# LiDAR_mainboard.net
KiCad netlist of a schematic drawn in Altium Designer
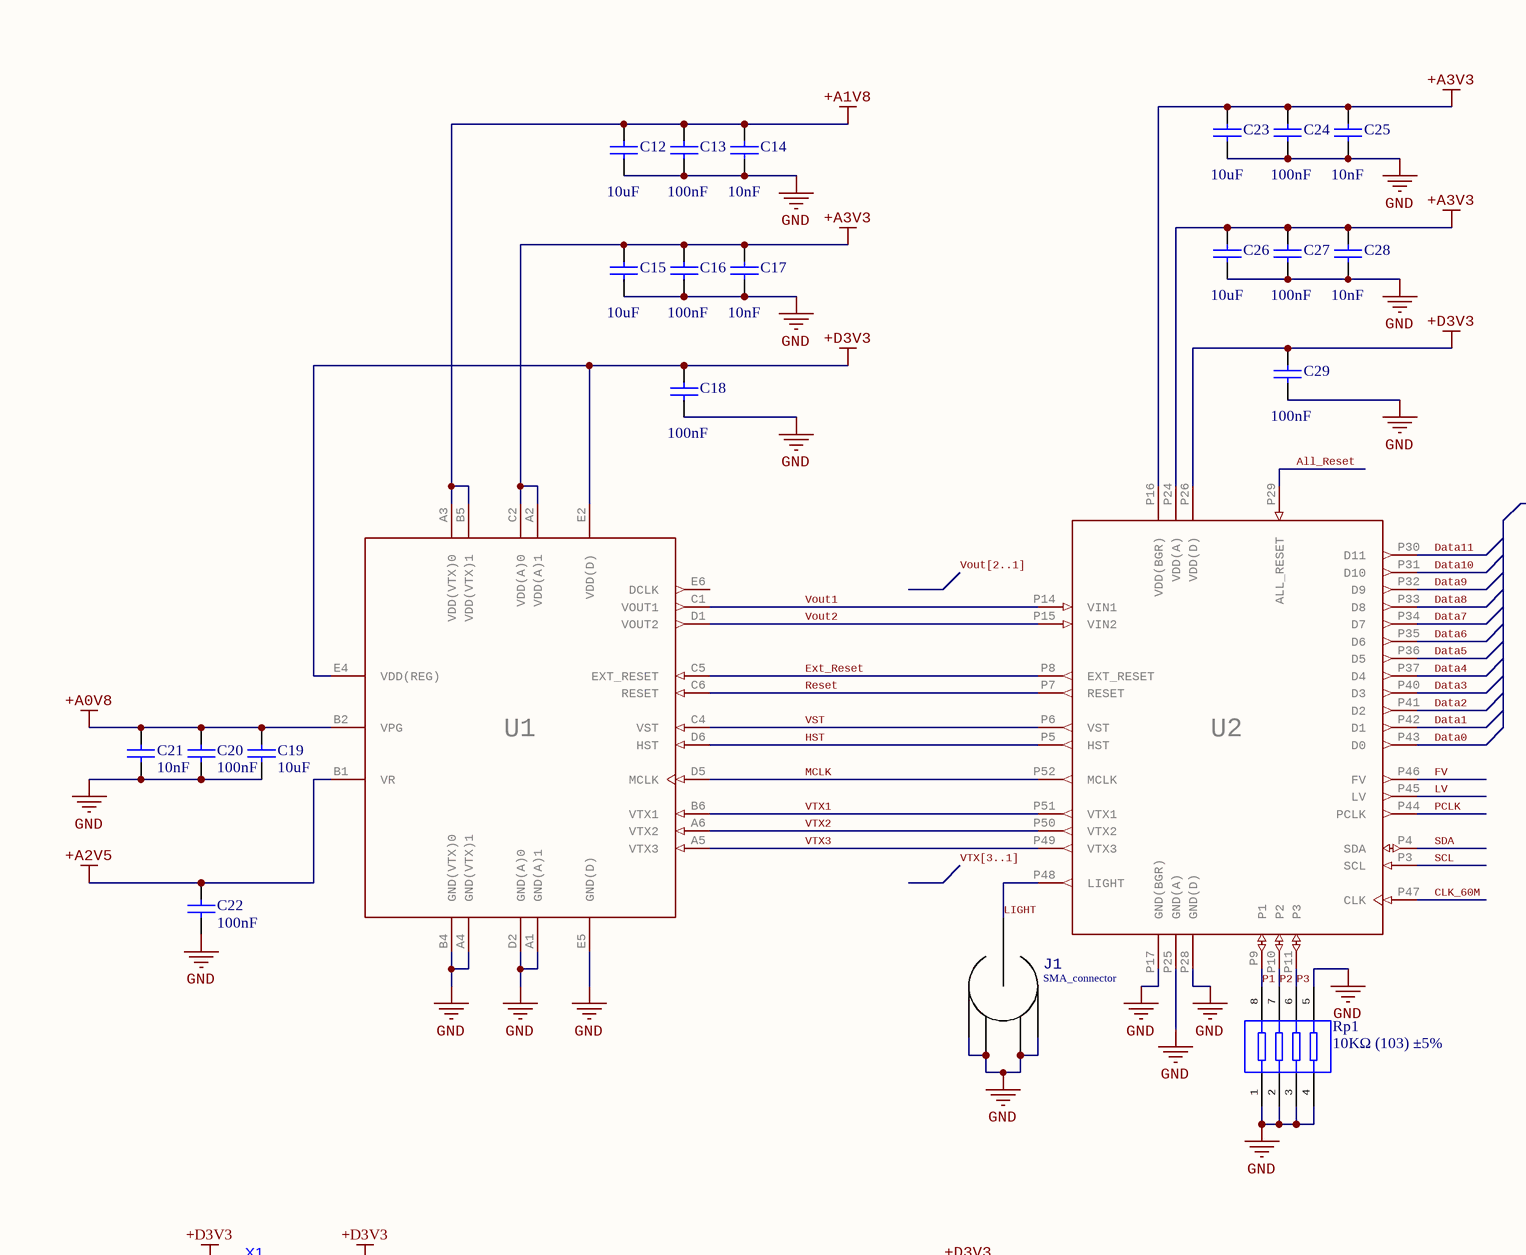
[diagram p0: LiDAR_mainboard.SchDoc, top left]
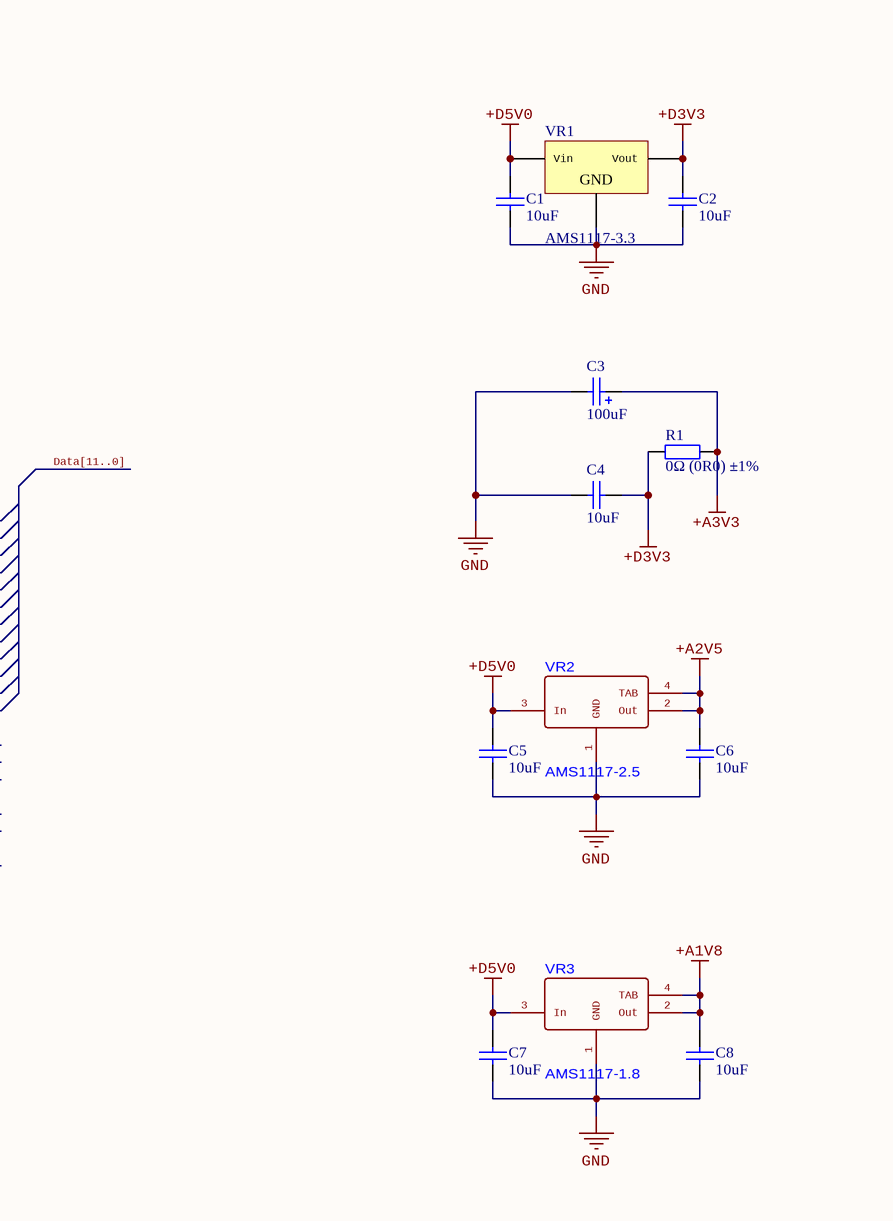
[diagram p1: LiDAR_mainboard.SchDoc, top right]
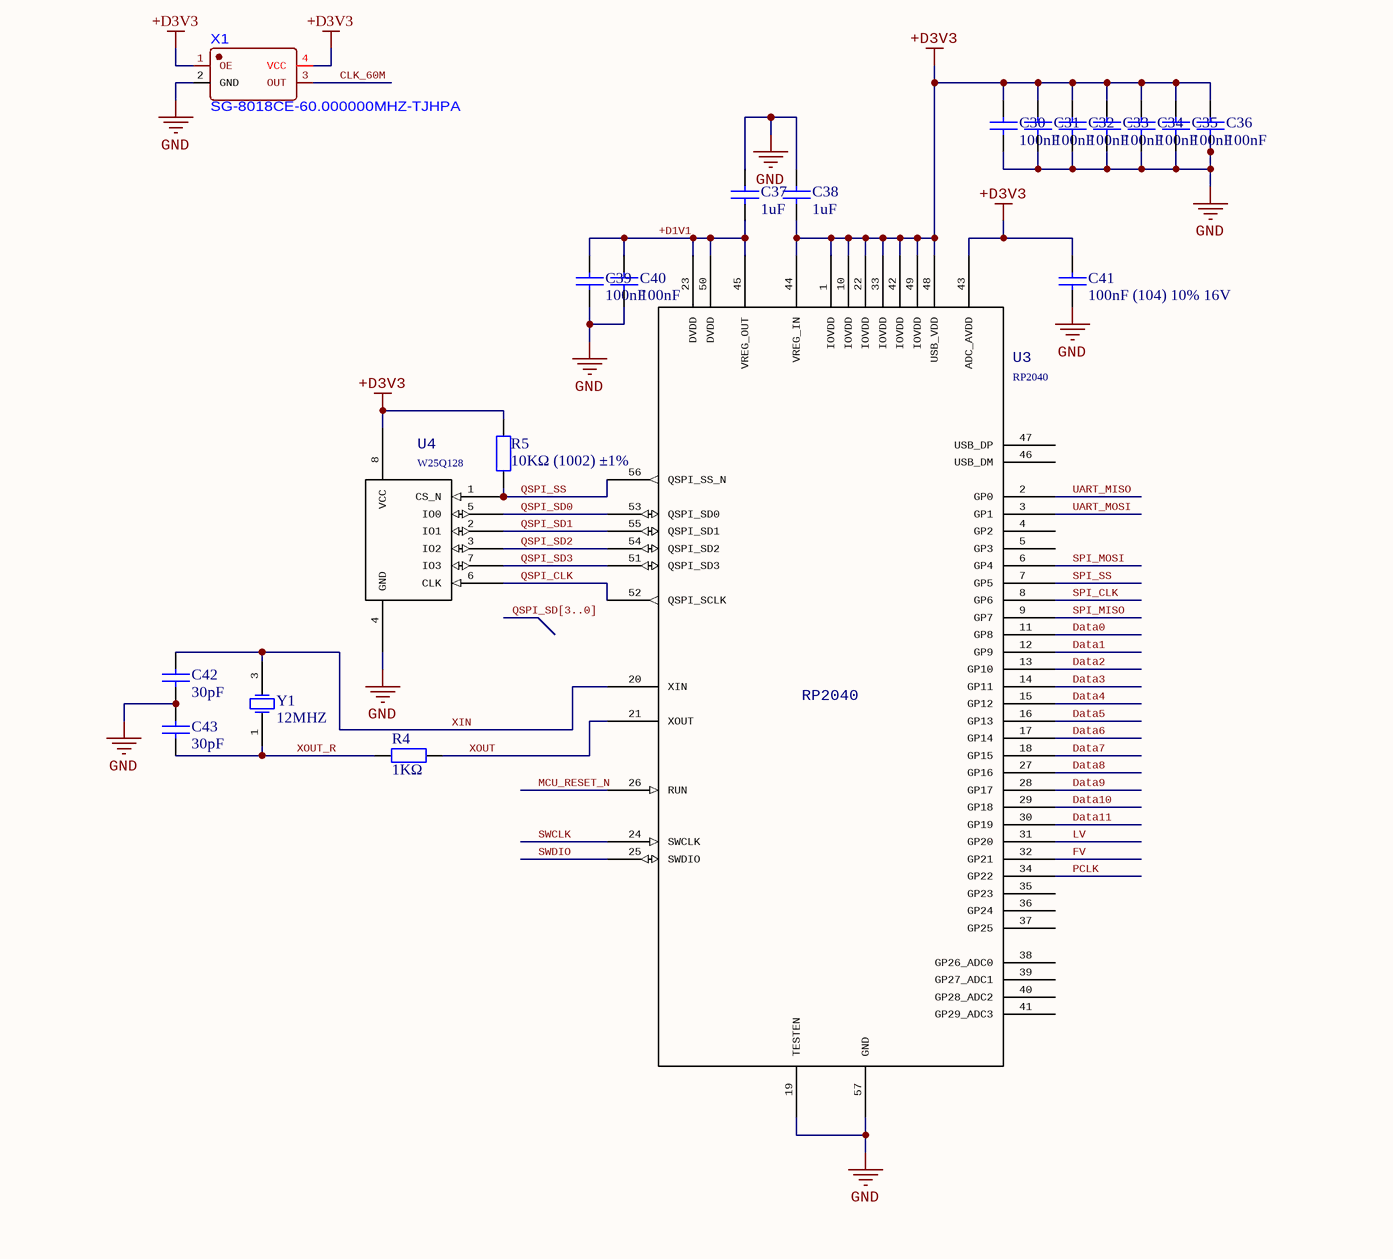
[diagram p2: LiDAR_mainboard.SchDoc, bottom left]
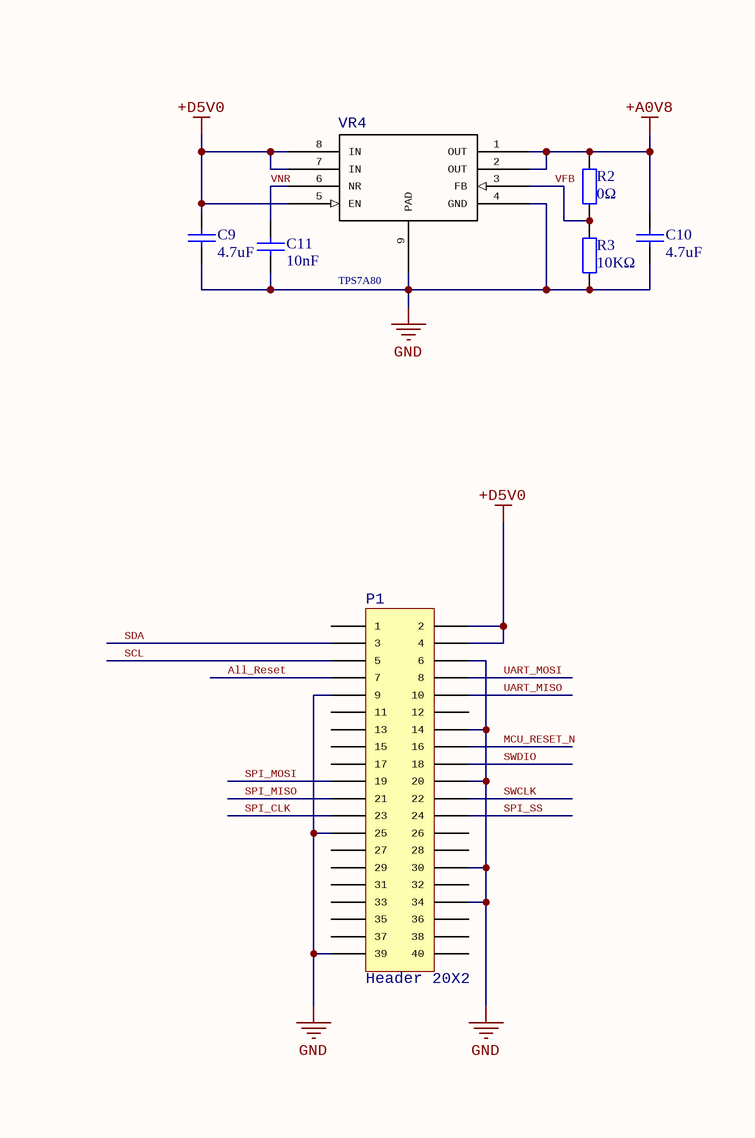
[diagram p3: LiDAR_mainboard.SchDoc, bottom right]

(export (version "E")
  (design (tool "Eeschema 10.0.6"))
  (components
    (comp (ref "C1")
      (value "10uF")
      (footprint "0402_C")
      (description "贴片电容")
      (libsource (lib "JLC SMT Devices") (part "0402 10uF (106) 20% 6.3V"))
    )
    (comp (ref "C2")
      (value "10uF")
      (footprint "0402_C")
      (description "贴片电容")
      (libsource (lib "JLC SMT Devices") (part "0402 10uF (106) 20% 6.3V"))
    )
    (comp (ref "C3")
      (value "100uF")
      (footprint "CASE-B_3528")
      (description "钽电容")
      (libsource (lib "JLC SMT Devices") (part "3528 100uF (107) 10% 6.3V"))
    )
    (comp (ref "C4")
      (value "10uF")
      (footprint "0603_C")
      (description "贴片电容")
      (libsource (lib "JLC SMT Devices") (part "0603 10uF (106) 10% 10V"))
    )
    (comp (ref "C5")
      (value "10uF")
      (footprint "0402_C")
      (description "贴片电容")
      (libsource (lib "JLC SMT Devices") (part "0402 10uF (106) 20% 6.3V"))
    )
    (comp (ref "C6")
      (value "10uF")
      (footprint "0402_C")
      (description "贴片电容")
      (libsource (lib "JLC SMT Devices") (part "0402 10uF (106) 20% 6.3V"))
    )
    (comp (ref "C7")
      (value "10uF")
      (footprint "0402_C")
      (description "贴片电容")
      (libsource (lib "JLC SMT Devices") (part "0402 10uF (106) 20% 6.3V"))
    )
    (comp (ref "C8")
      (value "10uF")
      (footprint "0402_C")
      (description "贴片电容")
      (libsource (lib "JLC SMT Devices") (part "0402 10uF (106) 20% 6.3V"))
    )
    (comp (ref "C9")
      (value "4.7uF")
      (footprint "0402_C")
      (description "贴片电容")
      (libsource (lib "JLC SMT Devices") (part "0402 4.7uF (475) 20% 10V"))
    )
    (comp (ref "C10")
      (value "4.7uF")
      (footprint "0402_C")
      (description "贴片电容")
      (libsource (lib "JLC SMT Devices") (part "0402 4.7uF (475) 20% 10V"))
    )
    (comp (ref "C11")
      (value "10nF")
      (footprint "0402_C")
      (description "贴片电容")
      (libsource (lib "JLC SMT Devices") (part "0402 10nF (103) 10% 50V"))
    )
    (comp (ref "C12")
      (value "10uF")
      (footprint "0402_C")
      (description "贴片电容")
      (libsource (lib "JLC SMT Devices") (part "0402 10uF (106) 20% 6.3V"))
    )
    (comp (ref "C13")
      (value "100nF")
      (footprint "0402_C")
      (description "贴片电容")
      (libsource (lib "JLC SMT Devices") (part "0402 100nF (104) 10% 16V"))
    )
    (comp (ref "C14")
      (value "10nF")
      (footprint "0402_C")
      (description "贴片电容")
      (libsource (lib "JLC SMT Devices") (part "0402 10nF (103) 10% 50V"))
    )
    (comp (ref "C15")
      (value "10uF")
      (footprint "0402_C")
      (description "贴片电容")
      (libsource (lib "JLC SMT Devices") (part "0402 10uF (106) 20% 6.3V"))
    )
    (comp (ref "C16")
      (value "100nF")
      (footprint "0402_C")
      (description "贴片电容")
      (libsource (lib "JLC SMT Devices") (part "0402 100nF (104) 10% 16V"))
    )
    (comp (ref "C17")
      (value "10nF")
      (footprint "0402_C")
      (description "贴片电容")
      (libsource (lib "JLC SMT Devices") (part "0402 10nF (103) 10% 50V"))
    )
    (comp (ref "C18")
      (value "100nF")
      (footprint "0402_C")
      (description "贴片电容")
      (libsource (lib "JLC SMT Devices") (part "0402 100nF (104) 10% 16V"))
    )
    (comp (ref "C19")
      (value "10uF")
      (footprint "0402_C")
      (description "贴片电容")
      (libsource (lib "JLC SMT Devices") (part "0402 10uF (106) 20% 6.3V"))
    )
    (comp (ref "C20")
      (value "100nF")
      (footprint "0402_C")
      (description "贴片电容")
      (libsource (lib "JLC SMT Devices") (part "0402 100nF (104) 10% 16V"))
    )
    (comp (ref "C21")
      (value "10nF")
      (footprint "0402_C")
      (description "贴片电容")
      (libsource (lib "JLC SMT Devices") (part "0402 10nF (103) 10% 50V"))
    )
    (comp (ref "C22")
      (value "100nF")
      (footprint "0402_C")
      (description "贴片电容")
      (libsource (lib "JLC SMT Devices") (part "0402 100nF (104) 10% 16V"))
    )
    (comp (ref "C23")
      (value "10uF")
      (footprint "0402_C")
      (description "贴片电容")
      (libsource (lib "JLC SMT Devices") (part "0402 10uF (106) 20% 6.3V"))
    )
    (comp (ref "C24")
      (value "100nF")
      (footprint "0402_C")
      (description "贴片电容")
      (libsource (lib "JLC SMT Devices") (part "0402 100nF (104) 10% 16V"))
    )
    (comp (ref "C25")
      (value "10nF")
      (footprint "0402_C")
      (description "贴片电容")
      (libsource (lib "JLC SMT Devices") (part "0402 10nF (103) 10% 50V"))
    )
    (comp (ref "C26")
      (value "10uF")
      (footprint "0402_C")
      (description "贴片电容")
      (libsource (lib "JLC SMT Devices") (part "0402 10uF (106) 20% 6.3V"))
    )
    (comp (ref "C27")
      (value "100nF")
      (footprint "0402_C")
      (description "贴片电容")
      (libsource (lib "JLC SMT Devices") (part "0402 100nF (104) 10% 16V"))
    )
    (comp (ref "C28")
      (value "10nF")
      (footprint "0402_C")
      (description "贴片电容")
      (libsource (lib "JLC SMT Devices") (part "0402 10nF (103) 10% 50V"))
    )
    (comp (ref "C29")
      (value "100nF")
      (footprint "0402_C")
      (description "贴片电容")
      (libsource (lib "JLC SMT Devices") (part "0402 100nF (104) 10% 16V"))
    )
    (comp (ref "C30")
      (value "100nF")
      (footprint "0402_C")
      (description "贴片电容")
      (libsource (lib "JLC SMT Devices") (part "0402 100nF (104) 10% 16V"))
    )
    (comp (ref "C31")
      (value "100nF")
      (footprint "0402_C")
      (description "贴片电容")
      (libsource (lib "JLC SMT Devices") (part "0402 100nF (104) 10% 16V"))
    )
    (comp (ref "C32")
      (value "100nF")
      (footprint "0402_C")
      (description "贴片电容")
      (libsource (lib "JLC SMT Devices") (part "0402 100nF (104) 10% 16V"))
    )
    (comp (ref "C33")
      (value "100nF")
      (footprint "0402_C")
      (description "贴片电容")
      (libsource (lib "JLC SMT Devices") (part "0402 100nF (104) 10% 16V"))
    )
    (comp (ref "C34")
      (value "100nF")
      (footprint "0402_C")
      (description "贴片电容")
      (libsource (lib "JLC SMT Devices") (part "0402 100nF (104) 10% 16V"))
    )
    (comp (ref "C35")
      (value "100nF")
      (footprint "0402_C")
      (description "贴片电容")
      (libsource (lib "JLC SMT Devices") (part "0402 100nF (104) 10% 16V"))
    )
    (comp (ref "C36")
      (value "100nF")
      (footprint "0402_C")
      (description "贴片电容")
      (libsource (lib "JLC SMT Devices") (part "0402 100nF (104) 10% 16V"))
    )
    (comp (ref "C37")
      (value "1uF")
      (footprint "0603_C")
      (description "贴片电容")
      (libsource (lib "JLC SMT Devices") (part "0603 1uF (105) 10% 50V"))
    )
    (comp (ref "C38")
      (value "1uF")
      (footprint "0603_C")
      (description "贴片电容")
      (libsource (lib "JLC SMT Devices") (part "0603 1uF (105) 10% 50V"))
    )
    (comp (ref "C39")
      (value "100nF")
      (footprint "0402_C")
      (description "贴片电容")
      (libsource (lib "JLC SMT Devices") (part "0402 100nF (104) 10% 16V"))
    )
    (comp (ref "C40")
      (value "100nF")
      (footprint "0402_C")
      (description "贴片电容")
      (libsource (lib "JLC SMT Devices") (part "0402 100nF (104) 10% 16V"))
    )
    (comp (ref "C41")
      (value "100nF (104) 10% 16V")
      (footprint "0402_C")
      (description "贴片电容")
      (libsource (lib "JLC SMT Devices") (part "0402 100nF (104) 10% 16V"))
    )
    (comp (ref "C42")
      (value "30pF")
      (footprint "0402_C")
      (description "贴片电容")
      (libsource (lib "JLC SMT Devices") (part "0402 30pF (300) 5% 50V"))
    )
    (comp (ref "C43")
      (value "30pF")
      (footprint "0402_C")
      (description "贴片电容")
      (libsource (lib "JLC SMT Devices") (part "0402 30pF (300) 5% 50V"))
    )
    (comp (ref "J1")
      (value "SMA_connector")
      (footprint "SMA_header")
      (libsource (lib "SMA connector") (part "SMA_connector"))
    )
    (comp (ref "P1")
      (value "Header 20X2")
      (footprint "HDR2X20")
      (description "Header, 20-Pin, Dual row")
      (fields (field (name "PUBLISHER") "Altium Limited"))
      (libsource (lib "Miscellaneous Connectors") (part "Header 20X2"))
    )
    (comp (ref "R1")
      (value "0Ω (0R0) ±1%")
      (footprint "0805_R")
      (description "贴片电阻")
      (libsource (lib "JLC SMT Devices") (part "0805 0Ω (0R0) 1%"))
    )
    (comp (ref "R2")
      (value "0Ω")
      (footprint "0603_R")
      (description "贴片电阻")
      (libsource (lib "JLC SMT Devices") (part "0603 0Ω (0R0) 1%"))
    )
    (comp (ref "R3")
      (value "10KΩ")
      (footprint "0603_R")
      (description "贴片电阻")
      (libsource (lib "JLC SMT Devices") (part "0603 10KΩ (1002) 1%"))
    )
    (comp (ref "R4")
      (value "1KΩ")
      (footprint "0402_R")
      (description "贴片电阻")
      (libsource (lib "JLC SMT Devices") (part "0402 1KΩ (1001) 1%"))
    )
    (comp (ref "R5")
      (value "10KΩ (1002) ±1%")
      (footprint "0603_R")
      (description "贴片电阻")
      (libsource (lib "JLC SMT Devices") (part "0603 10KΩ (1002) 1%"))
    )
    (comp (ref "Rp1")
      (value "10KΩ (103) ±5%")
      (footprint "0402_Rx4")
      (description "贴片排阻")
      (libsource (lib "JLC SMT Devices") (part "0402*4 10KΩ (103) 5%"))
    )
    (comp (ref "U1")
      (value "S15454-01WT Distance Area Image Sensor")
      (footprint "S15454-01WT")
      (description "Hamamatsu area distance image sensor")
      (libsource (lib "Hamamatsu Distance Image Sensors") (part "S15454-01WT"))
    )
    (comp (ref "U2")
      (value "H15472-01")
      (footprint "H15472-01")
      (description "ASIC for distance image sensors")
      (libsource (lib "Hamamatsu Distance Image Sensors") (part "H15472-01"))
    )
    (comp (ref "U3") (value "RP2040") (footprint "QFN-56") (libsource (lib "RP2040") (part "RP2040")))
    (comp (ref "U4") (value "W25Q128") (footprint "SOIC-8") (libsource (lib "W25Q128") (part "W25Q128")))
    (comp (ref "VR1")
      (value "AMS1117-3.3")
      (footprint "SOT-223")
      (description "低压差线性稳压(LDO)")
      (libsource (lib "JLC SMT Devices") (part "SOT-223 AMS1117-3.3"))
    )
    (comp (ref "VR2")
      (value "AMS1117-2.5")
      (footprint "SOT-223-4_L6.5-W3.5-P2.30-LS7.0-BR")
      (libsource (lib "AMS1117-2.5") (part "AMS1117-2.5"))
    )
    (comp (ref "VR3")
      (value "AMS1117-1.8")
      (footprint "SOT-223-4_L6.5-W3.5-P2.30-LS7.0-BR")
      (libsource (lib "AMS1117-1.8") (part "AMS1117-1.8"))
    )
    (comp (ref "VR4") (value "TPS7A80") (footprint "SON_8") (libsource (lib "TPS7A80") (part "TPS7A80")))
    (comp (ref "X1")
      (value "SG-8018CE-60.000000MHZ-TJHPA")
      (footprint "OSC-SMD_4P-L3.2-W2.5-BL_SIT8008BI")
      (libsource (lib "SG-8018CE-60.000000MHZ-TJHPA") (part "SG-8018CE-60.000000MHZ-TJHPA"))
    )
    (comp (ref "Y1")
      (value "12MHZ")
      (footprint "SMD-3225_4P")
      (description "贴片晶振")
      (libsource (lib "JLC SMT Devices") (part "SMD-3225_4P  12MHZ 20PF 10PPM"))
    )
  )
  (nets
    (net (code "1") (name "+A0V8") (class "Default")
      (node (ref "C10") (pin "2") (pinfunction "2_2") (pintype "passive"))
      (node (ref "C19") (pin "2") (pinfunction "2_2") (pintype "passive"))
      (node (ref "C20") (pin "2") (pinfunction "2_2") (pintype "passive"))
      (node (ref "C21") (pin "2") (pinfunction "2_2") (pintype "passive"))
      (node (ref "R2") (pin "2") (pinfunction "2_2") (pintype "passive"))
      (node (ref "U1") (pin "B2") (pinfunction "VPG_B2") (pintype "power_in"))
      (node (ref "VR4") (pin "1") (pinfunction "OUT_1") (pintype "power_in"))
      (node (ref "VR4") (pin "2") (pinfunction "OUT_2") (pintype "power_in"))
    )
    (net (code "2") (name "+A1V8") (class "Default")
      (node (ref "C12") (pin "2") (pinfunction "2_2") (pintype "passive"))
      (node (ref "C13") (pin "2") (pinfunction "2_2") (pintype "passive"))
      (node (ref "C14") (pin "2") (pinfunction "2_2") (pintype "passive"))
      (node (ref "C8") (pin "2") (pinfunction "2_2") (pintype "passive"))
      (node (ref "U1") (pin "A3") (pinfunction "VDD(VTX)0_A3") (pintype "power_in"))
      (node (ref "U1") (pin "B5") (pinfunction "VDD(VTX)1_B5") (pintype "power_in"))
      (node (ref "VR3") (pin "2") (pinfunction "Out_2") (pintype "passive"))
      (node (ref "VR3") (pin "4") (pinfunction "TAB_4") (pintype "passive"))
    )
    (net (code "3") (name "+A2V5") (class "Default")
      (node (ref "C22") (pin "2") (pinfunction "2_2") (pintype "passive"))
      (node (ref "C6") (pin "2") (pinfunction "2_2") (pintype "passive"))
      (node (ref "U1") (pin "B1") (pinfunction "VR_B1") (pintype "power_in"))
      (node (ref "VR2") (pin "2") (pinfunction "Out_2") (pintype "passive"))
      (node (ref "VR2") (pin "4") (pinfunction "TAB_4") (pintype "passive"))
    )
    (net (code "4") (name "+A3V3") (class "Default")
      (node (ref "C15") (pin "2") (pinfunction "2_2") (pintype "passive"))
      (node (ref "C16") (pin "2") (pinfunction "2_2") (pintype "passive"))
      (node (ref "C17") (pin "2") (pinfunction "2_2") (pintype "passive"))
      (node (ref "C23") (pin "2") (pinfunction "2_2") (pintype "passive"))
      (node (ref "C24") (pin "2") (pinfunction "2_2") (pintype "passive"))
      (node (ref "C25") (pin "2") (pinfunction "2_2") (pintype "passive"))
      (node (ref "C26") (pin "2") (pinfunction "2_2") (pintype "passive"))
      (node (ref "C27") (pin "2") (pinfunction "2_2") (pintype "passive"))
      (node (ref "C28") (pin "2") (pinfunction "2_2") (pintype "passive"))
      (node (ref "C3") (pin "1") (pinfunction "1_1") (pintype "passive"))
      (node (ref "R1") (pin "2") (pinfunction "2_2") (pintype "passive"))
      (node (ref "U1") (pin "A2") (pinfunction "VDD(A)1_A2") (pintype "power_in"))
      (node (ref "U1") (pin "C2") (pinfunction "VDD(A)0_C2") (pintype "power_in"))
      (node (ref "U2") (pin "P16") (pinfunction "VDD(BGR)_P16") (pintype "power_in"))
      (node (ref "U2") (pin "P24") (pinfunction "VDD(A)_P24") (pintype "power_in"))
    )
    (net (code "5") (name "+D3V3") (class "Default")
      (node (ref "C18") (pin "2") (pinfunction "2_2") (pintype "passive"))
      (node (ref "C2") (pin "2") (pinfunction "2_2") (pintype "passive"))
      (node (ref "C29") (pin "2") (pinfunction "2_2") (pintype "passive"))
      (node (ref "C30") (pin "2") (pinfunction "2_2") (pintype "passive"))
      (node (ref "C31") (pin "2") (pinfunction "2_2") (pintype "passive"))
      (node (ref "C32") (pin "2") (pinfunction "2_2") (pintype "passive"))
      (node (ref "C33") (pin "2") (pinfunction "2_2") (pintype "passive"))
      (node (ref "C34") (pin "2") (pinfunction "2_2") (pintype "passive"))
      (node (ref "C35") (pin "2") (pinfunction "2_2") (pintype "passive"))
      (node (ref "C36") (pin "2") (pinfunction "2_2") (pintype "passive"))
      (node (ref "C38") (pin "1") (pinfunction "1_1") (pintype "passive"))
      (node (ref "C4") (pin "1") (pinfunction "1_1") (pintype "passive"))
      (node (ref "C41") (pin "2") (pinfunction "2_2") (pintype "passive"))
      (node (ref "R1") (pin "1") (pinfunction "1_1") (pintype "passive"))
      (node (ref "R5") (pin "2") (pinfunction "2_2") (pintype "passive"))
      (node (ref "U1") (pin "E2") (pinfunction "VDD(D)_E2") (pintype "power_in"))
      (node (ref "U1") (pin "E4") (pinfunction "VDD(REG)_E4") (pintype "power_in"))
      (node (ref "U2") (pin "P26") (pinfunction "VDD(D)_P26") (pintype "power_in"))
      (node (ref "U3") (pin "1") (pinfunction "IOVDD_1") (pintype "power_in"))
      (node (ref "U3") (pin "10") (pinfunction "IOVDD_10") (pintype "power_in"))
      (node (ref "U3") (pin "22") (pinfunction "IOVDD_22") (pintype "power_in"))
      (node (ref "U3") (pin "33") (pinfunction "IOVDD_33") (pintype "power_in"))
      (node (ref "U3") (pin "42") (pinfunction "IOVDD_42") (pintype "power_in"))
      (node (ref "U3") (pin "43") (pinfunction "ADC_AVDD_43") (pintype "power_in"))
      (node (ref "U3") (pin "44") (pinfunction "VREG_IN_44") (pintype "power_in"))
      (node (ref "U3") (pin "48") (pinfunction "USB_VDD_48") (pintype "power_in"))
      (node (ref "U3") (pin "49") (pinfunction "IOVDD_49") (pintype "power_in"))
      (node (ref "U4") (pin "8") (pinfunction "VCC_8") (pintype "power_in"))
      (node (ref "VR1") (pin "2") (pinfunction "Vout_2") (pintype "passive"))
      (node (ref "X1") (pin "1") (pinfunction "OE_1") (pintype "passive"))
      (node (ref "X1") (pin "4") (pinfunction "VCC_4") (pintype "passive"))
    )
    (net (code "6") (name "+D5V0") (class "Default")
      (node (ref "C1") (pin "2") (pinfunction "2_2") (pintype "passive"))
      (node (ref "C5") (pin "2") (pinfunction "2_2") (pintype "passive"))
      (node (ref "C7") (pin "2") (pinfunction "2_2") (pintype "passive"))
      (node (ref "C9") (pin "2") (pinfunction "2_2") (pintype "passive"))
      (node (ref "P1") (pin "2") (pinfunction "2_2") (pintype "passive"))
      (node (ref "P1") (pin "4") (pinfunction "4_4") (pintype "passive"))
      (node (ref "VR1") (pin "3") (pinfunction "Vin_3") (pintype "passive"))
      (node (ref "VR2") (pin "3") (pinfunction "In_3") (pintype "passive"))
      (node (ref "VR3") (pin "3") (pinfunction "In_3") (pintype "passive"))
      (node (ref "VR4") (pin "5") (pinfunction "EN_5") (pintype "input"))
      (node (ref "VR4") (pin "7") (pinfunction "IN_7") (pintype "power_in"))
      (node (ref "VR4") (pin "8") (pinfunction "IN_8") (pintype "power_in"))
    )
    (net (code "7") (name "/+D1V1") (class "Default")
      (node (ref "C37") (pin "1") (pinfunction "1_1") (pintype "passive"))
      (node (ref "C39") (pin "2") (pinfunction "2_2") (pintype "passive"))
      (node (ref "C40") (pin "2") (pinfunction "2_2") (pintype "passive"))
      (node (ref "U3") (pin "23") (pinfunction "DVDD_23") (pintype "power_in"))
      (node (ref "U3") (pin "45") (pinfunction "VREG_OUT_45") (pintype "power_in"))
      (node (ref "U3") (pin "50") (pinfunction "DVDD_50") (pintype "power_in"))
    )
    (net (code "8") (name "/All_Reset") (class "Default")
      (node (ref "P1") (pin "7") (pinfunction "7_7") (pintype "passive"))
      (node (ref "U2") (pin "P29") (pinfunction "ALL_RESET_P29") (pintype "input"))
    )
    (net (code "9") (name "/CLK_60M") (class "Default")
      (node (ref "U2") (pin "P47") (pinfunction "CLK_P47") (pintype "input"))
      (node (ref "X1") (pin "3") (pinfunction "OUT_3") (pintype "passive"))
    )
    (net (code "10") (name "/Data0") (class "Default")
      (node (ref "U2") (pin "P43") (pinfunction "D0_P43") (pintype "output"))
      (node (ref "U3") (pin "11") (pinfunction "GP8_11") (pintype "passive"))
    )
    (net (code "11") (name "/Data1") (class "Default")
      (node (ref "U2") (pin "P42") (pinfunction "D1_P42") (pintype "output"))
      (node (ref "U3") (pin "12") (pinfunction "GP9_12") (pintype "passive"))
    )
    (net (code "12") (name "/Data2") (class "Default")
      (node (ref "U2") (pin "P41") (pinfunction "D2_P41") (pintype "output"))
      (node (ref "U3") (pin "13") (pinfunction "GP10_13") (pintype "passive"))
    )
    (net (code "13") (name "/Data3") (class "Default")
      (node (ref "U2") (pin "P40") (pinfunction "D3_P40") (pintype "output"))
      (node (ref "U3") (pin "14") (pinfunction "GP11_14") (pintype "passive"))
    )
    (net (code "14") (name "/Data4") (class "Default")
      (node (ref "U2") (pin "P37") (pinfunction "D4_P37") (pintype "output"))
      (node (ref "U3") (pin "15") (pinfunction "GP12_15") (pintype "passive"))
    )
    (net (code "15") (name "/Data5") (class "Default")
      (node (ref "U2") (pin "P36") (pinfunction "D5_P36") (pintype "output"))
      (node (ref "U3") (pin "16") (pinfunction "GP13_16") (pintype "passive"))
    )
    (net (code "16") (name "/Data6") (class "Default")
      (node (ref "U2") (pin "P35") (pinfunction "D6_P35") (pintype "output"))
      (node (ref "U3") (pin "17") (pinfunction "GP14_17") (pintype "passive"))
    )
    (net (code "17") (name "/Data7") (class "Default")
      (node (ref "U2") (pin "P34") (pinfunction "D7_P34") (pintype "output"))
      (node (ref "U3") (pin "18") (pinfunction "GP15_18") (pintype "passive"))
    )
    (net (code "18") (name "/Data8") (class "Default")
      (node (ref "U2") (pin "P33") (pinfunction "D8_P33") (pintype "output"))
      (node (ref "U3") (pin "27") (pinfunction "GP16_27") (pintype "passive"))
    )
    (net (code "19") (name "/Data9") (class "Default")
      (node (ref "U2") (pin "P32") (pinfunction "D9_P32") (pintype "output"))
      (node (ref "U3") (pin "28") (pinfunction "GP17_28") (pintype "passive"))
    )
    (net (code "20") (name "/Data10") (class "Default")
      (node (ref "U2") (pin "P31") (pinfunction "D10_P31") (pintype "output"))
      (node (ref "U3") (pin "29") (pinfunction "GP18_29") (pintype "passive"))
    )
    (net (code "21") (name "/Data11") (class "Default")
      (node (ref "U2") (pin "P30") (pinfunction "D11_P30") (pintype "output"))
      (node (ref "U3") (pin "30") (pinfunction "GP19_30") (pintype "passive"))
    )
    (net (code "23") (name "/Ext_Reset") (class "Default")
      (node (ref "U1") (pin "C5") (pinfunction "EXT_RESET_C5") (pintype "input"))
      (node (ref "U2") (pin "P8") (pinfunction "EXT_RESET_P8") (pintype "output"))
    )
    (net (code "24") (name "/FV") (class "Default")
      (node (ref "U2") (pin "P46") (pinfunction "FV_P46") (pintype "output"))
      (node (ref "U3") (pin "32") (pinfunction "GP21_32") (pintype "passive"))
    )
    (net (code "25") (name "/HST") (class "Default")
      (node (ref "U1") (pin "D6") (pinfunction "HST_D6") (pintype "input"))
      (node (ref "U2") (pin "P5") (pinfunction "HST_P5") (pintype "output"))
    )
    (net (code "26") (name "/LIGHT") (class "Default")
      (node (ref "J1") (pin "1") (pinfunction "CORE_1") (pintype "passive"))
      (node (ref "U2") (pin "P48") (pinfunction "LIGHT_P48") (pintype "output"))
    )
    (net (code "27") (name "/LV") (class "Default")
      (node (ref "U2") (pin "P45") (pinfunction "LV_P45") (pintype "output"))
      (node (ref "U3") (pin "31") (pinfunction "GP20_31") (pintype "passive"))
    )
    (net (code "28") (name "/MCLK") (class "Default")
      (node (ref "U1") (pin "D5") (pinfunction "MCLK_D5") (pintype "input"))
      (node (ref "U2") (pin "P52") (pinfunction "MCLK_P52") (pintype "output"))
    )
    (net (code "29") (name "/MCU_RESET_N") (class "Default")
      (node (ref "P1") (pin "16") (pinfunction "16_16") (pintype "passive"))
      (node (ref "U3") (pin "26") (pinfunction "RUN_26") (pintype "input"))
    )
    (net (code "30") (name "/P1") (class "Default")
      (node (ref "Rp1") (pin "8") (pinfunction "8_8") (pintype "passive"))
      (node (ref "U2") (pin "P9") (pinfunction "P1_P9") (pintype "bidirectional"))
    )
    (net (code "31") (name "/P2") (class "Default")
      (node (ref "Rp1") (pin "7") (pinfunction "7_7") (pintype "passive"))
      (node (ref "U2") (pin "P10") (pinfunction "P2_P10") (pintype "bidirectional"))
    )
    (net (code "32") (name "/P3") (class "Default")
      (node (ref "Rp1") (pin "6") (pinfunction "6_6") (pintype "passive"))
      (node (ref "U2") (pin "P11") (pinfunction "P3_P11") (pintype "bidirectional"))
    )
    (net (code "33") (name "/PCLK") (class "Default")
      (node (ref "U2") (pin "P44") (pinfunction "PCLK_P44") (pintype "output"))
      (node (ref "U3") (pin "34") (pinfunction "GP22_34") (pintype "passive"))
    )
    (net (code "34") (name "/QSPI_CLK") (class "Default")
      (node (ref "U3") (pin "52") (pinfunction "QSPI_SCLK_52") (pintype "output"))
      (node (ref "U4") (pin "6") (pinfunction "CLK_6") (pintype "input"))
    )
    (net (code "35") (name "/QSPI_SD0") (class "Default")
      (node (ref "U3") (pin "53") (pinfunction "QSPI_SD0_53") (pintype "bidirectional"))
      (node (ref "U4") (pin "5") (pinfunction "IO0_5") (pintype "bidirectional"))
    )
    (net (code "36") (name "/QSPI_SD1") (class "Default")
      (node (ref "U3") (pin "55") (pinfunction "QSPI_SD1_55") (pintype "bidirectional"))
      (node (ref "U4") (pin "2") (pinfunction "IO1_2") (pintype "bidirectional"))
    )
    (net (code "37") (name "/QSPI_SD2") (class "Default")
      (node (ref "U3") (pin "54") (pinfunction "QSPI_SD2_54") (pintype "bidirectional"))
      (node (ref "U4") (pin "3") (pinfunction "IO2_3") (pintype "bidirectional"))
    )
    (net (code "38") (name "/QSPI_SD3") (class "Default")
      (node (ref "U3") (pin "51") (pinfunction "QSPI_SD3_51") (pintype "bidirectional"))
      (node (ref "U4") (pin "7") (pinfunction "IO3_7") (pintype "bidirectional"))
    )
    (net (code "40") (name "/QSPI_SS") (class "Default")
      (node (ref "R5") (pin "1") (pinfunction "1_1") (pintype "passive"))
      (node (ref "U3") (pin "56") (pinfunction "QSPI_SS_N_56") (pintype "output"))
      (node (ref "U4") (pin "1") (pinfunction "CS_N_1") (pintype "input"))
    )
    (net (code "41") (name "/Reset") (class "Default")
      (node (ref "U1") (pin "C6") (pinfunction "RESET_C6") (pintype "input"))
      (node (ref "U2") (pin "P7") (pinfunction "RESET_P7") (pintype "output"))
    )
    (net (code "42") (name "/SCL") (class "Default")
      (node (ref "P1") (pin "5") (pinfunction "5_5") (pintype "passive"))
      (node (ref "U2") (pin "P3") (pinfunction "SCL_P3") (pintype "input"))
    )
    (net (code "43") (name "/SDA") (class "Default")
      (node (ref "P1") (pin "3") (pinfunction "3_3") (pintype "passive"))
      (node (ref "U2") (pin "P4") (pinfunction "SDA_P4") (pintype "bidirectional"))
    )
    (net (code "44") (name "/SPI_CLK") (class "Default")
      (node (ref "P1") (pin "23") (pinfunction "23_23") (pintype "passive"))
      (node (ref "U3") (pin "8") (pinfunction "GP6_8") (pintype "passive"))
    )
    (net (code "45") (name "/SPI_MISO") (class "Default")
      (node (ref "P1") (pin "21") (pinfunction "21_21") (pintype "passive"))
      (node (ref "U3") (pin "9") (pinfunction "GP7_9") (pintype "passive"))
    )
    (net (code "46") (name "/SPI_MOSI") (class "Default")
      (node (ref "P1") (pin "19") (pinfunction "19_19") (pintype "passive"))
      (node (ref "U3") (pin "6") (pinfunction "GP4_6") (pintype "passive"))
    )
    (net (code "47") (name "/SPI_SS") (class "Default")
      (node (ref "P1") (pin "24") (pinfunction "24_24") (pintype "passive"))
      (node (ref "U3") (pin "7") (pinfunction "GP5_7") (pintype "passive"))
    )
    (net (code "48") (name "/SWCLK") (class "Default")
      (node (ref "P1") (pin "22") (pinfunction "22_22") (pintype "passive"))
      (node (ref "U3") (pin "24") (pinfunction "SWCLK_24") (pintype "input"))
    )
    (net (code "49") (name "/SWDIO") (class "Default")
      (node (ref "P1") (pin "18") (pinfunction "18_18") (pintype "passive"))
      (node (ref "U3") (pin "25") (pinfunction "SWDIO_25") (pintype "bidirectional"))
    )
    (net (code "50") (name "/UART_MISO") (class "Default")
      (node (ref "P1") (pin "10") (pinfunction "10_10") (pintype "passive"))
      (node (ref "U3") (pin "2") (pinfunction "GP0_2") (pintype "passive"))
    )
    (net (code "51") (name "/UART_MOSI") (class "Default")
      (node (ref "P1") (pin "8") (pinfunction "8_8") (pintype "passive"))
      (node (ref "U3") (pin "3") (pinfunction "GP1_3") (pintype "passive"))
    )
    (net (code "52") (name "/VFB") (class "Default")
      (node (ref "R2") (pin "1") (pinfunction "1_1") (pintype "passive"))
      (node (ref "R3") (pin "2") (pinfunction "2_2") (pintype "passive"))
      (node (ref "VR4") (pin "3") (pinfunction "FB_3") (pintype "input"))
    )
    (net (code "53") (name "/VNR") (class "Default")
      (node (ref "C11") (pin "2") (pinfunction "2_2") (pintype "passive"))
      (node (ref "VR4") (pin "6") (pinfunction "NR_6") (pintype "passive"))
    )
    (net (code "54") (name "/VST") (class "Default")
      (node (ref "U1") (pin "C4") (pinfunction "VST_C4") (pintype "input"))
      (node (ref "U2") (pin "P6") (pinfunction "VST_P6") (pintype "output"))
    )
    (net (code "55") (name "/VTX1") (class "Default")
      (node (ref "U1") (pin "B6") (pinfunction "VTX1_B6") (pintype "input"))
      (node (ref "U2") (pin "P51") (pinfunction "VTX1_P51") (pintype "output"))
    )
    (net (code "56") (name "/VTX2") (class "Default")
      (node (ref "U1") (pin "A6") (pinfunction "VTX2_A6") (pintype "input"))
      (node (ref "U2") (pin "P50") (pinfunction "VTX2_P50") (pintype "output"))
    )
    (net (code "57") (name "/VTX3") (class "Default")
      (node (ref "U1") (pin "A5") (pinfunction "VTX3_A5") (pintype "input"))
      (node (ref "U2") (pin "P49") (pinfunction "VTX3_P49") (pintype "output"))
    )
    (net (code "59") (name "/Vout1") (class "Default")
      (node (ref "U1") (pin "C1") (pinfunction "VOUT1_C1") (pintype "output"))
      (node (ref "U2") (pin "P14") (pinfunction "VIN1_P14") (pintype "input"))
    )
    (net (code "60") (name "/Vout2") (class "Default")
      (node (ref "U1") (pin "D1") (pinfunction "VOUT2_D1") (pintype "output"))
      (node (ref "U2") (pin "P15") (pinfunction "VIN2_P15") (pintype "input"))
    )
    (net (code "62") (name "/XIN") (class "Default")
      (node (ref "C42") (pin "2") (pinfunction "2_2") (pintype "passive"))
      (node (ref "U3") (pin "20") (pinfunction "XIN_20") (pintype "passive"))
      (node (ref "Y1") (pin "3") (pinfunction "OSC2_3") (pintype "passive"))
    )
    (net (code "63") (name "/XOUT") (class "Default")
      (node (ref "R4") (pin "2") (pinfunction "2_2") (pintype "passive"))
      (node (ref "U3") (pin "21") (pinfunction "XOUT_21") (pintype "passive"))
    )
    (net (code "64") (name "/XOUT_R") (class "Default")
      (node (ref "C43") (pin "1") (pinfunction "1_1") (pintype "passive"))
      (node (ref "R4") (pin "1") (pinfunction "1_1") (pintype "passive"))
      (node (ref "Y1") (pin "1") (pinfunction "OSC1_1") (pintype "passive"))
    )
    (net (code "65") (name "GND") (class "Default")
      (node (ref "C1") (pin "1") (pinfunction "1_1") (pintype "passive"))
      (node (ref "C10") (pin "1") (pinfunction "1_1") (pintype "passive"))
      (node (ref "C11") (pin "1") (pinfunction "1_1") (pintype "passive"))
      (node (ref "C12") (pin "1") (pinfunction "1_1") (pintype "passive"))
      (node (ref "C13") (pin "1") (pinfunction "1_1") (pintype "passive"))
      (node (ref "C14") (pin "1") (pinfunction "1_1") (pintype "passive"))
      (node (ref "C15") (pin "1") (pinfunction "1_1") (pintype "passive"))
      (node (ref "C16") (pin "1") (pinfunction "1_1") (pintype "passive"))
      (node (ref "C17") (pin "1") (pinfunction "1_1") (pintype "passive"))
      (node (ref "C18") (pin "1") (pinfunction "1_1") (pintype "passive"))
      (node (ref "C19") (pin "1") (pinfunction "1_1") (pintype "passive"))
      (node (ref "C2") (pin "1") (pinfunction "1_1") (pintype "passive"))
      (node (ref "C20") (pin "1") (pinfunction "1_1") (pintype "passive"))
      (node (ref "C21") (pin "1") (pinfunction "1_1") (pintype "passive"))
      (node (ref "C22") (pin "1") (pinfunction "1_1") (pintype "passive"))
      (node (ref "C23") (pin "1") (pinfunction "1_1") (pintype "passive"))
      (node (ref "C24") (pin "1") (pinfunction "1_1") (pintype "passive"))
      (node (ref "C25") (pin "1") (pinfunction "1_1") (pintype "passive"))
      (node (ref "C26") (pin "1") (pinfunction "1_1") (pintype "passive"))
      (node (ref "C27") (pin "1") (pinfunction "1_1") (pintype "passive"))
      (node (ref "C28") (pin "1") (pinfunction "1_1") (pintype "passive"))
      (node (ref "C29") (pin "1") (pinfunction "1_1") (pintype "passive"))
      (node (ref "C3") (pin "2") (pinfunction "2_2") (pintype "passive"))
      (node (ref "C30") (pin "1") (pinfunction "1_1") (pintype "passive"))
      (node (ref "C31") (pin "1") (pinfunction "1_1") (pintype "passive"))
      (node (ref "C32") (pin "1") (pinfunction "1_1") (pintype "passive"))
      (node (ref "C33") (pin "1") (pinfunction "1_1") (pintype "passive"))
      (node (ref "C34") (pin "1") (pinfunction "1_1") (pintype "passive"))
      (node (ref "C35") (pin "1") (pinfunction "1_1") (pintype "passive"))
      (node (ref "C36") (pin "1") (pinfunction "1_1") (pintype "passive"))
      (node (ref "C37") (pin "2") (pinfunction "2_2") (pintype "passive"))
      (node (ref "C38") (pin "2") (pinfunction "2_2") (pintype "passive"))
      (node (ref "C39") (pin "1") (pinfunction "1_1") (pintype "passive"))
      (node (ref "C4") (pin "2") (pinfunction "2_2") (pintype "passive"))
      (node (ref "C40") (pin "1") (pinfunction "1_1") (pintype "passive"))
      (node (ref "C41") (pin "1") (pinfunction "1_1") (pintype "passive"))
      (node (ref "C42") (pin "1") (pinfunction "1_1") (pintype "passive"))
      (node (ref "C43") (pin "2") (pinfunction "2_2") (pintype "passive"))
      (node (ref "C5") (pin "1") (pinfunction "1_1") (pintype "passive"))
      (node (ref "C6") (pin "1") (pinfunction "1_1") (pintype "passive"))
      (node (ref "C7") (pin "1") (pinfunction "1_1") (pintype "passive"))
      (node (ref "C8") (pin "1") (pinfunction "1_1") (pintype "passive"))
      (node (ref "C9") (pin "1") (pinfunction "1_1") (pintype "passive"))
      (node (ref "J1") (pin "2") (pinfunction "GND_2") (pintype "passive"))
      (node (ref "J1") (pin "3") (pinfunction "GND_3") (pintype "passive"))
      (node (ref "J1") (pin "4") (pinfunction "GND_4") (pintype "passive"))
      (node (ref "J1") (pin "5") (pinfunction "GND_5") (pintype "passive"))
      (node (ref "P1") (pin "14") (pinfunction "14_14") (pintype "passive"))
      (node (ref "P1") (pin "20") (pinfunction "20_20") (pintype "passive"))
      (node (ref "P1") (pin "25") (pinfunction "25_25") (pintype "passive"))
      (node (ref "P1") (pin "30") (pinfunction "30_30") (pintype "passive"))
      (node (ref "P1") (pin "34") (pinfunction "34_34") (pintype "passive"))
      (node (ref "P1") (pin "39") (pinfunction "39_39") (pintype "passive"))
      (node (ref "P1") (pin "6") (pinfunction "6_6") (pintype "passive"))
      (node (ref "P1") (pin "9") (pinfunction "9_9") (pintype "passive"))
      (node (ref "R3") (pin "1") (pinfunction "1_1") (pintype "passive"))
      (node (ref "Rp1") (pin "1") (pinfunction "1_1") (pintype "passive"))
      (node (ref "Rp1") (pin "2") (pinfunction "2_2") (pintype "passive"))
      (node (ref "Rp1") (pin "3") (pinfunction "3_3") (pintype "passive"))
      (node (ref "Rp1") (pin "4") (pinfunction "4_4") (pintype "passive"))
      (node (ref "Rp1") (pin "5") (pinfunction "5_5") (pintype "passive"))
      (node (ref "U1") (pin "A1") (pinfunction "GND(A)1_A1") (pintype "power_in"))
      (node (ref "U1") (pin "A4") (pinfunction "GND(VTX)1_A4") (pintype "power_in"))
      (node (ref "U1") (pin "B4") (pinfunction "GND(VTX)0_B4") (pintype "power_in"))
      (node (ref "U1") (pin "D2") (pinfunction "GND(A)0_D2") (pintype "power_in"))
      (node (ref "U1") (pin "E5") (pinfunction "GND(D)_E5") (pintype "power_in"))
      (node (ref "U2") (pin "P17") (pinfunction "GND(BGR)_P17") (pintype "power_in"))
      (node (ref "U2") (pin "P25") (pinfunction "GND(A)_P25") (pintype "power_in"))
      (node (ref "U2") (pin "P28") (pinfunction "GND(D)_P28") (pintype "power_in"))
      (node (ref "U3") (pin "19") (pinfunction "TESTEN_19") (pintype "passive"))
      (node (ref "U3") (pin "57") (pinfunction "GND_57") (pintype "power_in"))
      (node (ref "U4") (pin "4") (pinfunction "GND_4") (pintype "power_in"))
      (node (ref "VR1") (pin "1") (pinfunction "GND_1") (pintype "passive"))
      (node (ref "VR2") (pin "1") (pinfunction "GND_1") (pintype "passive"))
      (node (ref "VR3") (pin "1") (pinfunction "GND_1") (pintype "passive"))
      (node (ref "VR4") (pin "4") (pinfunction "GND_4") (pintype "power_in"))
      (node (ref "VR4") (pin "9") (pinfunction "PAD_9") (pintype "power_in"))
      (node (ref "X1") (pin "2") (pinfunction "GND_2") (pintype "passive"))
    )
    (net (code "66") (name "unconnected-(P1-Pad1)") (class "Default")
      (node (ref "P1") (pin "1") (pinfunction "1_1") (pintype "passive"))
    )
    (net (code "67") (name "unconnected-(P1-Pad11)") (class "Default")
      (node (ref "P1") (pin "11") (pinfunction "11_11") (pintype "passive"))
    )
    (net (code "68") (name "unconnected-(P1-Pad12)") (class "Default")
      (node (ref "P1") (pin "12") (pinfunction "12_12") (pintype "passive"))
    )
    (net (code "69") (name "unconnected-(P1-Pad13)") (class "Default")
      (node (ref "P1") (pin "13") (pinfunction "13_13") (pintype "passive"))
    )
    (net (code "70") (name "unconnected-(P1-Pad15)") (class "Default")
      (node (ref "P1") (pin "15") (pinfunction "15_15") (pintype "passive"))
    )
    (net (code "71") (name "unconnected-(P1-Pad17)") (class "Default")
      (node (ref "P1") (pin "17") (pinfunction "17_17") (pintype "passive"))
    )
    (net (code "72") (name "unconnected-(P1-Pad26)") (class "Default")
      (node (ref "P1") (pin "26") (pinfunction "26_26") (pintype "passive"))
    )
    (net (code "73") (name "unconnected-(P1-Pad27)") (class "Default")
      (node (ref "P1") (pin "27") (pinfunction "27_27") (pintype "passive"))
    )
    (net (code "74") (name "unconnected-(P1-Pad28)") (class "Default")
      (node (ref "P1") (pin "28") (pinfunction "28_28") (pintype "passive"))
    )
    (net (code "75") (name "unconnected-(P1-Pad29)") (class "Default")
      (node (ref "P1") (pin "29") (pinfunction "29_29") (pintype "passive"))
    )
    (net (code "76") (name "unconnected-(P1-Pad31)") (class "Default")
      (node (ref "P1") (pin "31") (pinfunction "31_31") (pintype "passive"))
    )
    (net (code "77") (name "unconnected-(P1-Pad32)") (class "Default")
      (node (ref "P1") (pin "32") (pinfunction "32_32") (pintype "passive"))
    )
    (net (code "78") (name "unconnected-(P1-Pad33)") (class "Default")
      (node (ref "P1") (pin "33") (pinfunction "33_33") (pintype "passive"))
    )
    (net (code "79") (name "unconnected-(P1-Pad35)") (class "Default")
      (node (ref "P1") (pin "35") (pinfunction "35_35") (pintype "passive"))
    )
    (net (code "80") (name "unconnected-(P1-Pad36)") (class "Default")
      (node (ref "P1") (pin "36") (pinfunction "36_36") (pintype "passive"))
    )
    (net (code "81") (name "unconnected-(P1-Pad37)") (class "Default")
      (node (ref "P1") (pin "37") (pinfunction "37_37") (pintype "passive"))
    )
    (net (code "82") (name "unconnected-(P1-Pad38)") (class "Default")
      (node (ref "P1") (pin "38") (pinfunction "38_38") (pintype "passive"))
    )
    (net (code "83") (name "unconnected-(P1-Pad40)") (class "Default")
      (node (ref "P1") (pin "40") (pinfunction "40_40") (pintype "passive"))
    )
    (net (code "84") (name "unconnected-(U1-DCLK-PadE6)") (class "Default")
      (node (ref "U1") (pin "E6") (pinfunction "DCLK_E6") (pintype "output"))
    )
    (net (code "85") (name "unconnected-(U3-GP2-Pad4)") (class "Default")
      (node (ref "U3") (pin "4") (pinfunction "GP2_4") (pintype "passive"))
    )
    (net (code "86") (name "unconnected-(U3-GP3-Pad5)") (class "Default")
      (node (ref "U3") (pin "5") (pinfunction "GP3_5") (pintype "passive"))
    )
    (net (code "87") (name "unconnected-(U3-GP23-Pad35)") (class "Default")
      (node (ref "U3") (pin "35") (pinfunction "GP23_35") (pintype "passive"))
    )
    (net (code "88") (name "unconnected-(U3-GP24-Pad36)") (class "Default")
      (node (ref "U3") (pin "36") (pinfunction "GP24_36") (pintype "passive"))
    )
    (net (code "89") (name "unconnected-(U3-GP25-Pad37)") (class "Default")
      (node (ref "U3") (pin "37") (pinfunction "GP25_37") (pintype "passive"))
    )
    (net (code "90") (name "unconnected-(U3-GP26_ADC0-Pad38)") (class "Default")
      (node (ref "U3") (pin "38") (pinfunction "GP26_ADC0_38") (pintype "passive"))
    )
    (net (code "91") (name "unconnected-(U3-GP27_ADC1-Pad39)") (class "Default")
      (node (ref "U3") (pin "39") (pinfunction "GP27_ADC1_39") (pintype "passive"))
    )
    (net (code "92") (name "unconnected-(U3-GP28_ADC2-Pad40)") (class "Default")
      (node (ref "U3") (pin "40") (pinfunction "GP28_ADC2_40") (pintype "passive"))
    )
    (net (code "93") (name "unconnected-(U3-GP29_ADC3-Pad41)") (class "Default")
      (node (ref "U3") (pin "41") (pinfunction "GP29_ADC3_41") (pintype "passive"))
    )
    (net (code "94") (name "unconnected-(U3-USB_DM-Pad46)") (class "Default")
      (node (ref "U3") (pin "46") (pinfunction "USB_DM_46") (pintype "passive"))
    )
    (net (code "95") (name "unconnected-(U3-USB_DP-Pad47)") (class "Default")
      (node (ref "U3") (pin "47") (pinfunction "USB_DP_47") (pintype "passive"))
    )
  )
)
